# pcb.net
KiCad netlist of a schematic drawn in EasyEDA
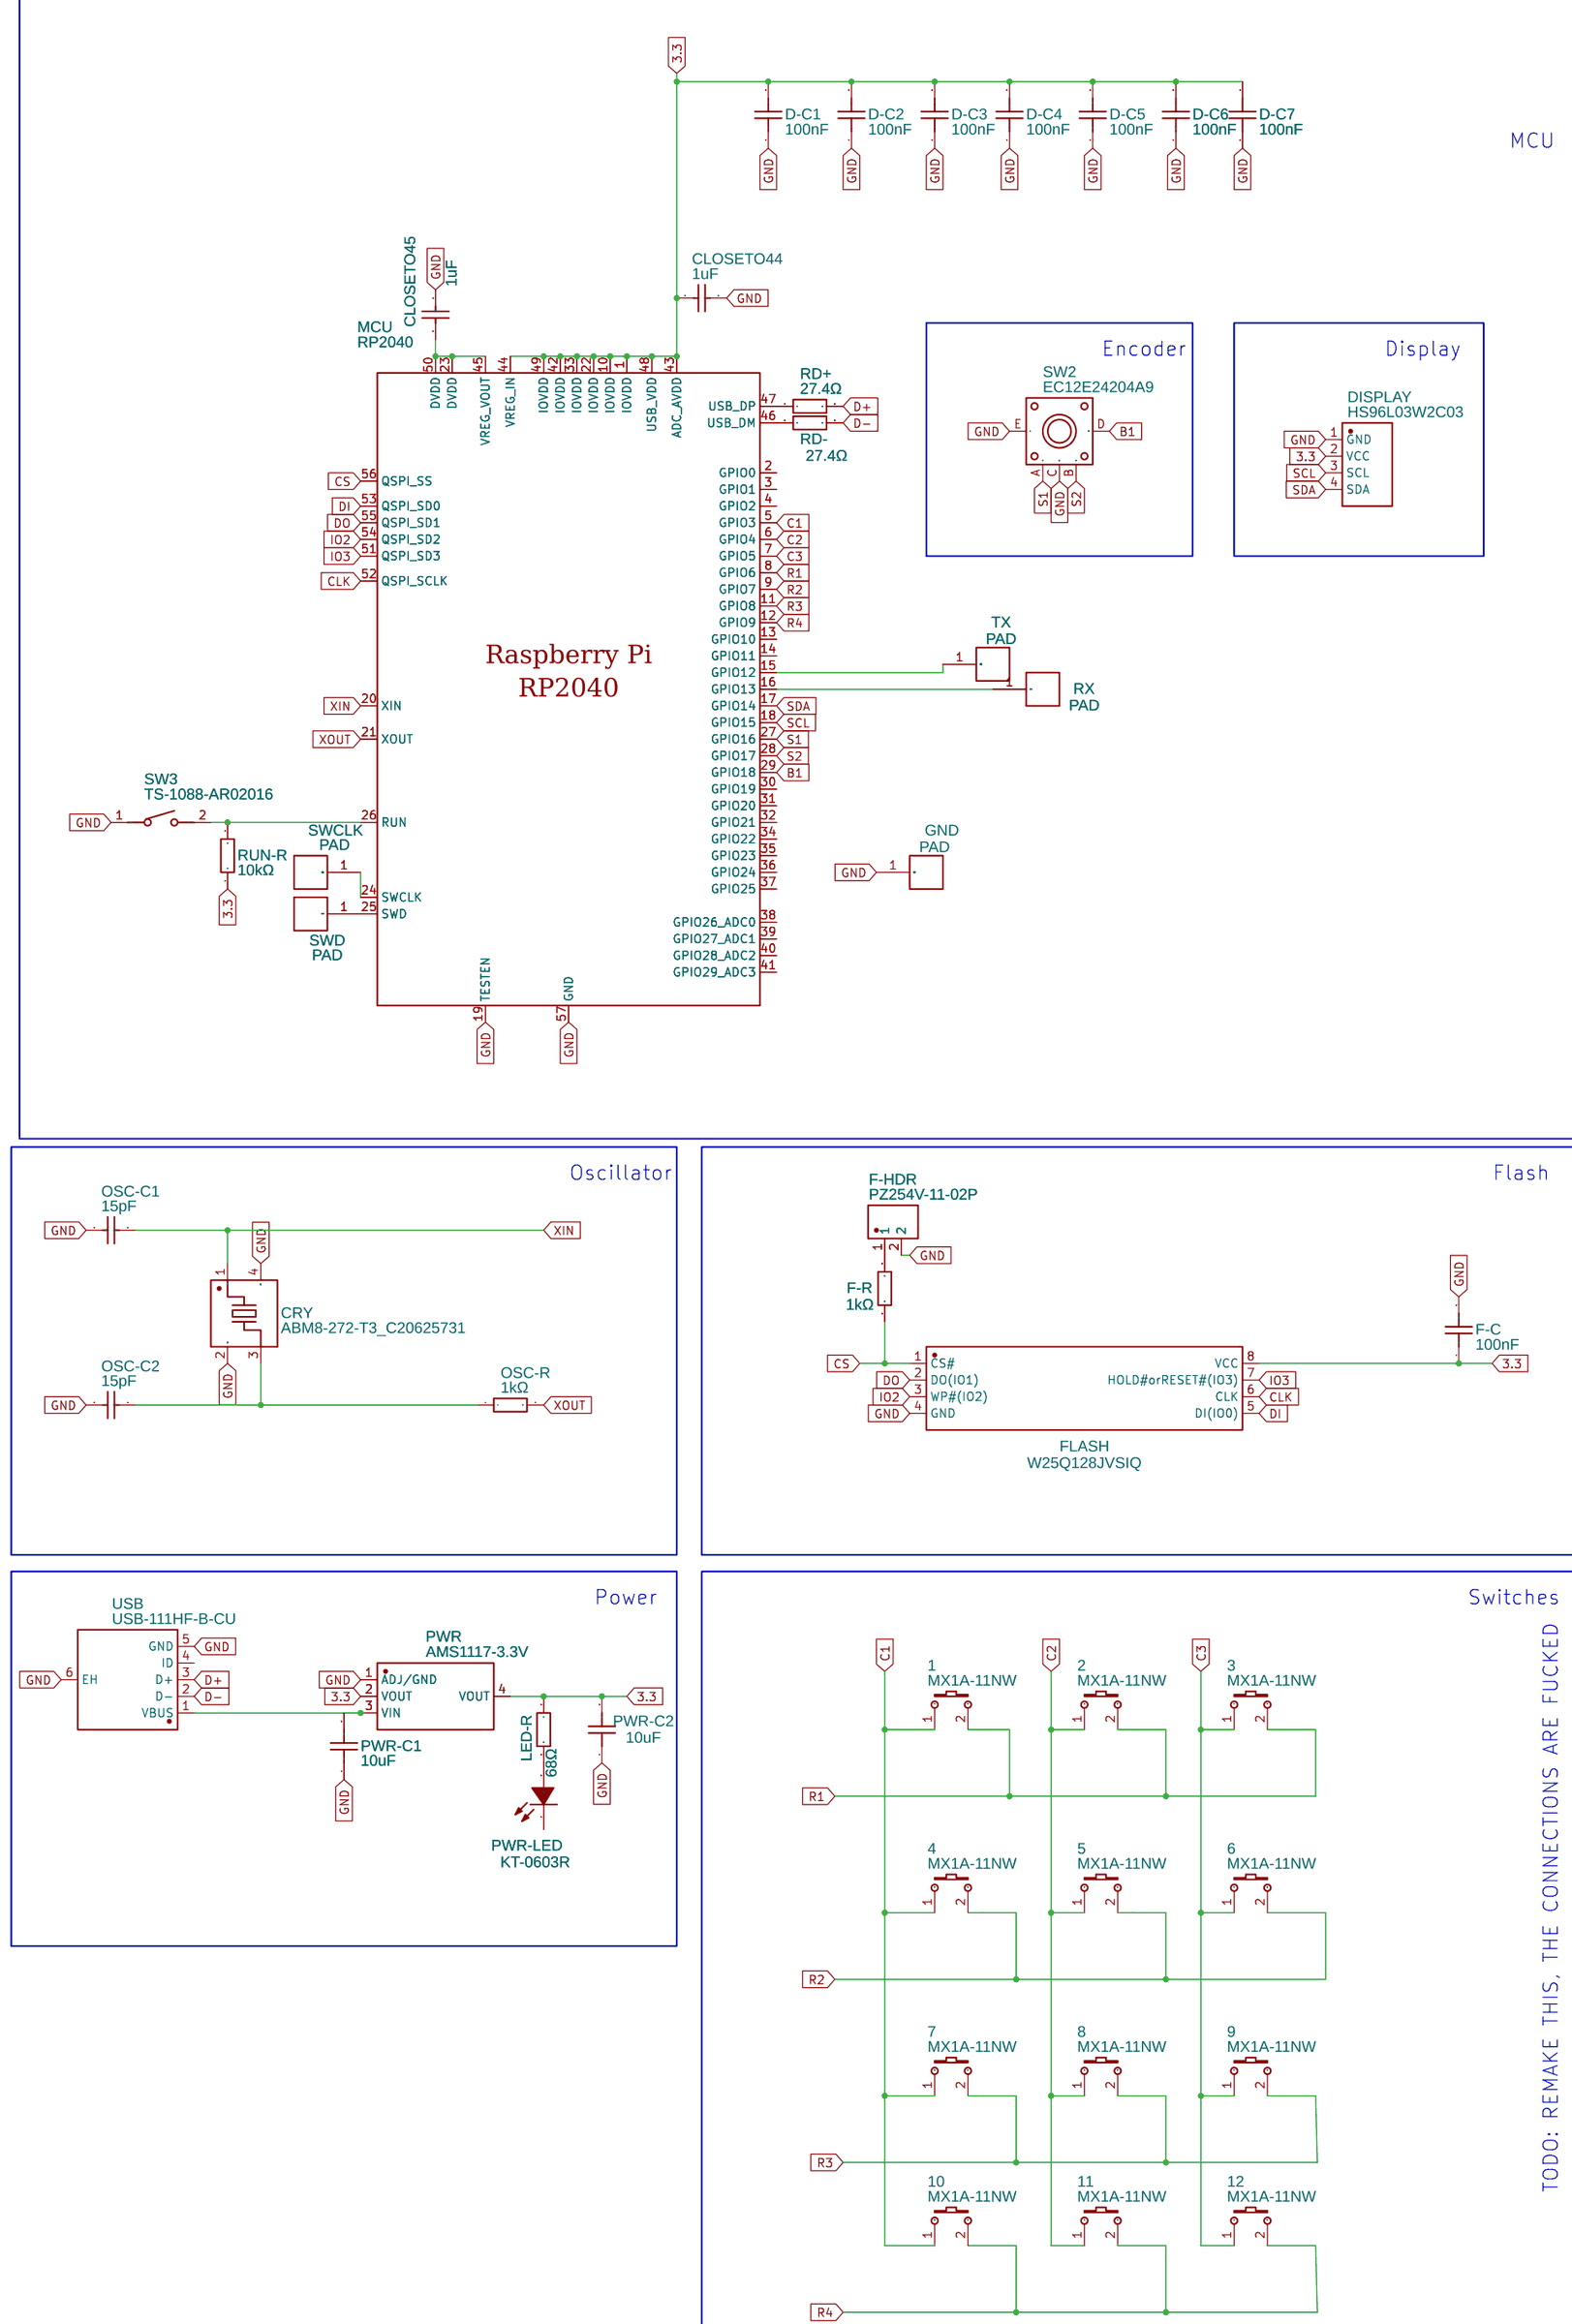
[diagram p0: schematic sheet]

(export (version "E")
  (design (tool "Eeschema 10.0.6"))
  (components
    (comp (ref "1")
      (value "MX1A-11NW")
      (fields (field (name "Manufacturer") "CHERRY"))
      (libsource (lib "") (part "MX1A-11NW"))
    )
    (comp (ref "2")
      (value "MX1A-11NW")
      (fields (field (name "Manufacturer") "CHERRY"))
      (libsource (lib "") (part "MX1A-11NW"))
    )
    (comp (ref "3")
      (value "MX1A-11NW")
      (fields (field (name "Manufacturer") "CHERRY"))
      (libsource (lib "") (part "MX1A-11NW"))
    )
    (comp (ref "4")
      (value "MX1A-11NW")
      (fields (field (name "Manufacturer") "CHERRY"))
      (libsource (lib "") (part "MX1A-11NW"))
    )
    (comp (ref "5")
      (value "MX1A-11NW")
      (fields (field (name "Manufacturer") "CHERRY"))
      (libsource (lib "") (part "MX1A-11NW"))
    )
    (comp (ref "6")
      (value "MX1A-11NW")
      (fields (field (name "Manufacturer") "CHERRY"))
      (libsource (lib "") (part "MX1A-11NW"))
    )
    (comp (ref "7")
      (value "MX1A-11NW")
      (fields (field (name "Manufacturer") "CHERRY"))
      (libsource (lib "") (part "MX1A-11NW"))
    )
    (comp (ref "8")
      (value "MX1A-11NW")
      (fields (field (name "Manufacturer") "CHERRY"))
      (libsource (lib "") (part "MX1A-11NW"))
    )
    (comp (ref "9")
      (value "MX1A-11NW")
      (fields (field (name "Manufacturer") "CHERRY"))
      (libsource (lib "") (part "MX1A-11NW"))
    )
    (comp (ref "10")
      (value "MX1A-11NW")
      (fields (field (name "Manufacturer") "CHERRY"))
      (libsource (lib "") (part "MX1A-11NW"))
    )
    (comp (ref "11")
      (value "MX1A-11NW")
      (fields (field (name "Manufacturer") "CHERRY"))
      (libsource (lib "") (part "MX1A-11NW"))
    )
    (comp (ref "12")
      (value "MX1A-11NW")
      (fields (field (name "Manufacturer") "CHERRY"))
      (libsource (lib "") (part "MX1A-11NW"))
    )
    (comp (ref "CLOSETO44")
      (value "1uF")
      (fields
        (field (name "Manufacturer Part") "GRM155R61E105KA12D")
        (field (name "Manufacturer") "muRata(村田)")
      )
      (libsource (lib "") (part "GRM155R61E105KA12D_1"))
    )
    (comp (ref "CLOSETO45")
      (value "1uF")
      (fields
        (field (name "Manufacturer Part") "GRM155R61E105KA12D")
        (field (name "Manufacturer") "muRata(村田)")
      )
      (libsource (lib "") (part "GRM155R61E105KA12D"))
    )
    (comp (ref "CRY")
      (value "ABM8-272-T3_C20625731")
      (fields (field (name "Manufacturer Part") "ABM8-272-T3") (field (name "Manufacturer") "ABRACON"))
      (libsource (lib "") (part "ABM8-272-T3_C20625731"))
    )
    (comp (ref "D-C1")
      (value "100nF")
      (fields
        (field (name "Manufacturer Part") "CC0603KRX7R9BB104")
        (field (name "Manufacturer") "YAGEO(国巨)")
      )
      (libsource (lib "") (part "CC0603KRX7R9BB104"))
    )
    (comp (ref "D-C2")
      (value "100nF")
      (fields
        (field (name "Manufacturer Part") "CC0603KRX7R9BB104")
        (field (name "Manufacturer") "YAGEO(国巨)")
      )
      (libsource (lib "") (part "CC0603KRX7R9BB104"))
    )
    (comp (ref "D-C3")
      (value "100nF")
      (fields
        (field (name "Manufacturer Part") "CC0603KRX7R9BB104")
        (field (name "Manufacturer") "YAGEO(国巨)")
      )
      (libsource (lib "") (part "CC0603KRX7R9BB104"))
    )
    (comp (ref "D-C4")
      (value "100nF")
      (fields
        (field (name "Manufacturer Part") "CC0603KRX7R9BB104")
        (field (name "Manufacturer") "YAGEO(国巨)")
      )
      (libsource (lib "") (part "CC0603KRX7R9BB104"))
    )
    (comp (ref "D-C5")
      (value "100nF")
      (fields
        (field (name "Manufacturer Part") "CC0603KRX7R9BB104")
        (field (name "Manufacturer") "YAGEO(国巨)")
      )
      (libsource (lib "") (part "CC0603KRX7R9BB104"))
    )
    (comp (ref "D-C6")
      (value "100nF")
      (fields
        (field (name "Manufacturer Part") "CC0603KRX7R9BB104")
        (field (name "Manufacturer") "YAGEO(国巨)")
      )
      (libsource (lib "") (part "CC0603KRX7R9BB104"))
    )
    (comp (ref "D-C7")
      (value "100nF")
      (fields
        (field (name "Manufacturer Part") "CC0603KRX7R9BB104")
        (field (name "Manufacturer") "YAGEO(国巨)")
      )
      (libsource (lib "") (part "CC0603KRX7R9BB104"))
    )
    (comp (ref "DISPLAY")
      (value "HS96L03W2C03")
      (fields (field (name "Manufacturer") "HS(汉昇)"))
      (libsource (lib "") (part "HS96L03W2C03"))
    )
    (comp (ref "F-C")
      (value "100nF")
      (fields
        (field (name "Manufacturer Part") "CC0603KRX7R9BB104")
        (field (name "Manufacturer") "YAGEO(国巨)")
      )
      (libsource (lib "") (part "CC0603KRX7R9BB104_1"))
    )
    (comp (ref "F-HDR")
      (value "PZ254V-11-02P")
      (fields (field (name "Manufacturer") "XFCN(兴飞)"))
      (libsource (lib "") (part "PZ254V-11-02P"))
    )
    (comp (ref "F-R")
      (value "1kΩ")
      (fields
        (field (name "Manufacturer Part") "0805W8F1001T5E")
        (field (name "Manufacturer") "UNI-ROYAL(厚声)")
      )
      (libsource (lib "") (part "0805W8F1001T5E_1"))
    )
    (comp (ref "FLASH")
      (value "W25Q128JVSIQ")
      (fields (field (name "Manufacturer") "WINBOND(华邦)"))
      (libsource (lib "") (part "W25Q128JVSIQ"))
    )
    (comp (ref "GND") (value "PAD") (libsource (lib "") (part "PAD_4")))
    (comp (ref "LED-R")
      (value "68Ω")
      (fields
        (field (name "Manufacturer Part") "1206W4F680JT5E")
        (field (name "Manufacturer") "UNI-ROYAL(厚声)")
      )
      (libsource (lib "") (part "1206W4F680JT5E"))
    )
    (comp (ref "MCU")
      (value "RP2040")
      (fields (field (name "Manufacturer") "Raspberry Pi(树莓派)"))
      (libsource (lib "") (part "RP2040"))
    )
    (comp (ref "OSC-C1")
      (value "15pF")
      (fields (field (name "Manufacturer Part") "0805CG150J500NT") (field (name "Manufacturer") "FH(风华)"))
      (libsource (lib "") (part "0805CG150J500NT"))
    )
    (comp (ref "OSC-C2")
      (value "15pF")
      (fields (field (name "Manufacturer Part") "0805CG150J500NT") (field (name "Manufacturer") "FH(风华)"))
      (libsource (lib "") (part "0805CG150J500NT"))
    )
    (comp (ref "OSC-R")
      (value "1kΩ")
      (fields
        (field (name "Manufacturer Part") "0805W8F1001T5E")
        (field (name "Manufacturer") "UNI-ROYAL(厚声)")
      )
      (libsource (lib "") (part "0805W8F1001T5E"))
    )
    (comp (ref "PWR")
      (value "AMS1117-3.3V")
      (fields (field (name "Manufacturer") "WPMtek(维攀)"))
      (libsource (lib "") (part "AMS1117-3.3V"))
    )
    (comp (ref "PWR-C1")
      (value "10uF")
      (fields
        (field (name "Manufacturer Part") "CL21A106KAYNNNE")
        (field (name "Manufacturer") "SAMSUNG(三星)")
      )
      (libsource (lib "") (part "CL21A106KAYNNNE"))
    )
    (comp (ref "PWR-C2")
      (value "10uF")
      (fields
        (field (name "Manufacturer Part") "CL21A106KAYNNNE")
        (field (name "Manufacturer") "SAMSUNG(三星)")
      )
      (libsource (lib "") (part "CL21A106KAYNNNE"))
    )
    (comp (ref "PWR-LED")
      (value "KT-0603R")
      (fields (field (name "Manufacturer") "KENTO"))
      (libsource (lib "") (part "KT-0603R"))
    )
    (comp (ref "RD+")
      (value "27.4Ω")
      (fields (field (name "Manufacturer Part") "RS-03K27R4FT") (field (name "Manufacturer") "FH(风华)"))
      (libsource (lib "") (part "RS-03K27R4FT"))
    )
    (comp (ref "RD-")
      (value "27.4Ω")
      (fields (field (name "Manufacturer Part") "RS-03K27R4FT") (field (name "Manufacturer") "FH(风华)"))
      (libsource (lib "") (part "RS-03K27R4FT_1"))
    )
    (comp (ref "RUN-R")
      (value "10kΩ")
      (fields
        (field (name "Manufacturer Part") "0805W8F1002T5E")
        (field (name "Manufacturer") "UNI-ROYAL(厚声)")
      )
      (libsource (lib "") (part "0805W8F1002T5E"))
    )
    (comp (ref "RX") (value "PAD") (libsource (lib "") (part "PAD")))
    (comp (ref "SW2")
      (value "EC12E24204A9")
      (fields (field (name "Manufacturer") "ALPSALPINE(阿尔卑斯阿尔派)"))
      (libsource (lib "") (part "EC12E24204A9"))
    )
    (comp (ref "SW3")
      (value "TS-1088-AR02016")
      (fields (field (name "Manufacturer") "XUNPU(讯普)"))
      (libsource (lib "") (part "TS-1088-AR02016"))
    )
    (comp (ref "SWCLK") (value "PAD") (libsource (lib "") (part "PAD_2")))
    (comp (ref "SWD") (value "PAD") (libsource (lib "") (part "PAD_1")))
    (comp (ref "TX") (value "PAD") (libsource (lib "") (part "PAD_3")))
    (comp (ref "USB")
      (value "USB-111HF-B-CU")
      (fields (field (name "Manufacturer") "HOOYA(皓宇电子)"))
      (libsource (lib "") (part "USB-111HF-B-CU"))
    )
  )
  (nets
    (net (code "1") (name "3.3") (class "Default")
      (node (ref "CLOSETO44") (pin "1") (pinfunction "1_1") (pintype "input"))
      (node (ref "D-C1") (pin "2") (pinfunction "2_2") (pintype "unspecified"))
      (node (ref "D-C2") (pin "2") (pinfunction "2_2") (pintype "unspecified"))
      (node (ref "D-C3") (pin "2") (pinfunction "2_2") (pintype "unspecified"))
      (node (ref "D-C4") (pin "2") (pinfunction "2_2") (pintype "unspecified"))
      (node (ref "D-C5") (pin "2") (pinfunction "2_2") (pintype "unspecified"))
      (node (ref "D-C6") (pin "2") (pinfunction "2_2") (pintype "unspecified"))
      (node (ref "D-C7") (pin "2") (pinfunction "2_2") (pintype "unspecified"))
      (node (ref "DISPLAY") (pin "2") (pinfunction "VCC_2") (pintype "unspecified"))
      (node (ref "F-C") (pin "1") (pinfunction "1_1") (pintype "unspecified"))
      (node (ref "FLASH") (pin "8") (pinfunction "VCC_8") (pintype "unspecified"))
      (node (ref "LED-R") (pin "1") (pinfunction "1_1") (pintype "input"))
      (node (ref "MCU") (pin "1") (pinfunction "IOVDD_1") (pintype "bidirectional"))
      (node (ref "MCU") (pin "10") (pinfunction "IOVDD_10") (pintype "bidirectional"))
      (node (ref "MCU") (pin "22") (pinfunction "IOVDD_22") (pintype "bidirectional"))
      (node (ref "MCU") (pin "33") (pinfunction "IOVDD_33") (pintype "bidirectional"))
      (node (ref "MCU") (pin "42") (pinfunction "IOVDD_42") (pintype "bidirectional"))
      (node (ref "MCU") (pin "43") (pinfunction "ADC_AVDD_43") (pintype "bidirectional"))
      (node (ref "MCU") (pin "44") (pinfunction "VREG_IN_44") (pintype "bidirectional"))
      (node (ref "MCU") (pin "48") (pinfunction "USB_VDD_48") (pintype "bidirectional"))
      (node (ref "MCU") (pin "49") (pinfunction "IOVDD_49") (pintype "bidirectional"))
      (node (ref "PWR") (pin "2") (pinfunction "VOUT_2") (pintype "unspecified"))
      (node (ref "PWR") (pin "4") (pinfunction "VOUT_4") (pintype "unspecified"))
      (node (ref "PWR-C2") (pin "2") (pinfunction "2_2") (pintype "unspecified"))
      (node (ref "RUN-R") (pin "2") (pinfunction "2_2") (pintype "input"))
    )
    (net (code "2") (name "B1") (class "Default")
      (node (ref "MCU") (pin "29") (pinfunction "GPIO18_29") (pintype "bidirectional"))
      (node (ref "SW2") (pin "D") (pinfunction "D_D") (pintype "unspecified"))
    )
    (net (code "3") (name "C1") (class "Default")
      (node (ref "1") (pin "1") (pinfunction "1_1") (pintype "unspecified"))
      (node (ref "10") (pin "1") (pinfunction "1_1") (pintype "unspecified"))
      (node (ref "4") (pin "1") (pinfunction "1_1") (pintype "unspecified"))
      (node (ref "7") (pin "1") (pinfunction "1_1") (pintype "unspecified"))
      (node (ref "MCU") (pin "5") (pinfunction "GPIO3_5") (pintype "bidirectional"))
    )
    (net (code "4") (name "C2") (class "Default")
      (node (ref "11") (pin "1") (pinfunction "1_1") (pintype "unspecified"))
      (node (ref "2") (pin "1") (pinfunction "1_1") (pintype "unspecified"))
      (node (ref "5") (pin "1") (pinfunction "1_1") (pintype "unspecified"))
      (node (ref "8") (pin "1") (pinfunction "1_1") (pintype "unspecified"))
      (node (ref "MCU") (pin "6") (pinfunction "GPIO4_6") (pintype "bidirectional"))
    )
    (net (code "5") (name "C3") (class "Default")
      (node (ref "12") (pin "1") (pinfunction "1_1") (pintype "unspecified"))
      (node (ref "3") (pin "1") (pinfunction "1_1") (pintype "unspecified"))
      (node (ref "6") (pin "1") (pinfunction "1_1") (pintype "unspecified"))
      (node (ref "9") (pin "1") (pinfunction "1_1") (pintype "unspecified"))
      (node (ref "MCU") (pin "7") (pinfunction "GPIO5_7") (pintype "bidirectional"))
    )
    (net (code "6") (name "CLK") (class "Default")
      (node (ref "FLASH") (pin "6") (pinfunction "CLK_6") (pintype "unspecified"))
      (node (ref "MCU") (pin "52") (pinfunction "QSPI_SCLK_52") (pintype "output"))
    )
    (net (code "7") (name "CS") (class "Default")
      (node (ref "F-R") (pin "2") (pinfunction "2_2") (pintype "input"))
      (node (ref "FLASH") (pin "1") (pinfunction "CS#_1") (pintype "unspecified"))
      (node (ref "MCU") (pin "56") (pinfunction "QSPI_SS_56") (pintype "bidirectional"))
    )
    (net (code "8") (name "D+") (class "Default")
      (node (ref "RD+") (pin "2") (pinfunction "2_2") (pintype "unspecified"))
      (node (ref "USB") (pin "3") (pinfunction "D+_3") (pintype "unspecified"))
    )
    (net (code "9") (name "D-") (class "Default")
      (node (ref "RD-") (pin "2") (pinfunction "2_2") (pintype "unspecified"))
      (node (ref "USB") (pin "2") (pinfunction "D-_2") (pintype "unspecified"))
    )
    (net (code "10") (name "DI") (class "Default")
      (node (ref "FLASH") (pin "5") (pinfunction "DI(IO0)_5") (pintype "unspecified"))
      (node (ref "MCU") (pin "53") (pinfunction "QSPI_SD0_53") (pintype "bidirectional"))
    )
    (net (code "11") (name "DO") (class "Default")
      (node (ref "FLASH") (pin "2") (pinfunction "DO(IO1)_2") (pintype "unspecified"))
      (node (ref "MCU") (pin "55") (pinfunction "QSPI_SD1_55") (pintype "bidirectional"))
    )
    (net (code "12") (name "GND") (class "Default")
      (node (ref "CLOSETO44") (pin "2") (pinfunction "2_2") (pintype "input"))
      (node (ref "CLOSETO45") (pin "1") (pinfunction "1_1") (pintype "input"))
      (node (ref "CRY") (pin "2") (pinfunction "GND_2") (pintype "input"))
      (node (ref "CRY") (pin "4") (pinfunction "GND_4") (pintype "input"))
      (node (ref "D-C1") (pin "1") (pinfunction "1_1") (pintype "unspecified"))
      (node (ref "D-C2") (pin "1") (pinfunction "1_1") (pintype "unspecified"))
      (node (ref "D-C3") (pin "1") (pinfunction "1_1") (pintype "unspecified"))
      (node (ref "D-C4") (pin "1") (pinfunction "1_1") (pintype "unspecified"))
      (node (ref "D-C5") (pin "1") (pinfunction "1_1") (pintype "unspecified"))
      (node (ref "D-C6") (pin "1") (pinfunction "1_1") (pintype "unspecified"))
      (node (ref "D-C7") (pin "1") (pinfunction "1_1") (pintype "unspecified"))
      (node (ref "DISPLAY") (pin "1") (pinfunction "GND_1") (pintype "unspecified"))
      (node (ref "F-C") (pin "2") (pinfunction "2_2") (pintype "unspecified"))
      (node (ref "F-HDR") (pin "2") (pinfunction "2_2") (pintype "unspecified"))
      (node (ref "FLASH") (pin "4") (pinfunction "GND_4") (pintype "unspecified"))
      (node (ref "GND") (pin "1") (pinfunction "PADPAD123_1") (pintype "unspecified"))
      (node (ref "MCU") (pin "19") (pinfunction "TESTEN_19") (pintype "unspecified"))
      (node (ref "MCU") (pin "57") (pinfunction "GND_57") (pintype "bidirectional"))
      (node (ref "OSC-C1") (pin "2") (pinfunction "2_2") (pintype "input"))
      (node (ref "OSC-C2") (pin "2") (pinfunction "2_2") (pintype "input"))
      (node (ref "PWR") (pin "1") (pinfunction "ADJ/GND_1") (pintype "unspecified"))
      (node (ref "PWR-C1") (pin "1") (pinfunction "1_1") (pintype "unspecified"))
      (node (ref "PWR-C2") (pin "1") (pinfunction "1_1") (pintype "unspecified"))
      (node (ref "SW2") (pin "C") (pinfunction "C_C") (pintype "unspecified"))
      (node (ref "SW2") (pin "E") (pinfunction "E_E") (pintype "unspecified"))
      (node (ref "SW3") (pin "1") (pinfunction "1_1") (pintype "unspecified"))
      (node (ref "USB") (pin "5") (pinfunction "GND_5") (pintype "unspecified"))
      (node (ref "USB") (pin "6") (pinfunction "EH_6") (pintype "unspecified"))
    )
    (net (code "13") (name "IO2") (class "Default")
      (node (ref "FLASH") (pin "3") (pinfunction "WP#(IO2)_3") (pintype "unspecified"))
      (node (ref "MCU") (pin "54") (pinfunction "QSPI_SD2_54") (pintype "bidirectional"))
    )
    (net (code "14") (name "IO3") (class "Default")
      (node (ref "FLASH") (pin "7") (pinfunction "HOLD#orRESET#(IO3)_7") (pintype "unspecified"))
      (node (ref "MCU") (pin "51") (pinfunction "QSPI_SD3_51") (pintype "bidirectional"))
    )
    (net (code "15") (name "Net-(CRY-Pad3)") (class "Default")
      (node (ref "CRY") (pin "3") (pinfunction "3_3") (pintype "input"))
      (node (ref "OSC-C2") (pin "1") (pinfunction "1_1") (pintype "input"))
      (node (ref "OSC-R") (pin "1") (pinfunction "1_1") (pintype "input"))
    )
    (net (code "16") (name "Net-(F-HDR-Pad1)") (class "Default")
      (node (ref "F-HDR") (pin "1") (pinfunction "1_1") (pintype "unspecified"))
      (node (ref "F-R") (pin "1") (pinfunction "1_1") (pintype "input"))
    )
    (net (code "17") (name "Net-(MCU-GPIO12)") (class "Default")
      (node (ref "MCU") (pin "15") (pinfunction "GPIO12_15") (pintype "bidirectional"))
      (node (ref "TX") (pin "1") (pinfunction "PADPAD123_1") (pintype "unspecified"))
    )
    (net (code "18") (name "Net-(MCU-GPIO13)") (class "Default")
      (node (ref "MCU") (pin "16") (pinfunction "GPIO13_16") (pintype "bidirectional"))
      (node (ref "RX") (pin "1") (pinfunction "PADPAD123_1") (pintype "unspecified"))
    )
    (net (code "19") (name "Net-(MCU-RUN)") (class "Default")
      (node (ref "MCU") (pin "26") (pinfunction "RUN_26") (pintype "input"))
      (node (ref "RUN-R") (pin "1") (pinfunction "1_1") (pintype "input"))
      (node (ref "SW3") (pin "2") (pinfunction "2_2") (pintype "unspecified"))
    )
    (net (code "20") (name "Net-(MCU-SWCLK)") (class "Default")
      (node (ref "MCU") (pin "24") (pinfunction "SWCLK_24") (pintype "output"))
      (node (ref "SWCLK") (pin "1") (pinfunction "PADPAD123_1") (pintype "unspecified"))
    )
    (net (code "21") (name "Net-(MCU-SWD)") (class "Default")
      (node (ref "MCU") (pin "25") (pinfunction "SWD_25") (pintype "bidirectional"))
      (node (ref "SWD") (pin "1") (pinfunction "PADPAD123_1") (pintype "unspecified"))
    )
    (net (code "22") (name "Net-(MCU-USB_DM)") (class "Default")
      (node (ref "MCU") (pin "46") (pinfunction "USB_DM_46") (pintype "bidirectional"))
      (node (ref "RD-") (pin "1") (pinfunction "1_1") (pintype "unspecified"))
    )
    (net (code "23") (name "Net-(MCU-USB_DP)") (class "Default")
      (node (ref "MCU") (pin "47") (pinfunction "USB_DP_47") (pintype "bidirectional"))
      (node (ref "RD+") (pin "1") (pinfunction "1_1") (pintype "unspecified"))
    )
    (net (code "24") (name "Net-(MCU-VREG_VOUT)") (class "Default")
      (node (ref "CLOSETO45") (pin "2") (pinfunction "2_2") (pintype "input"))
      (node (ref "MCU") (pin "23") (pinfunction "DVDD_23") (pintype "bidirectional"))
      (node (ref "MCU") (pin "45") (pinfunction "VREG_VOUT_45") (pintype "bidirectional"))
      (node (ref "MCU") (pin "50") (pinfunction "DVDD_50") (pintype "bidirectional"))
    )
    (net (code "25") (name "Net-(PWR-LED-A)") (class "Default")
      (node (ref "LED-R") (pin "2") (pinfunction "2_2") (pintype "input"))
      (node (ref "PWR-LED") (pin "2") (pinfunction "A_2") (pintype "unspecified"))
    )
    (net (code "26") (name "Net-(PWR-VIN)") (class "Default")
      (node (ref "PWR") (pin "3") (pinfunction "VIN_3") (pintype "unspecified"))
      (node (ref "PWR-C1") (pin "2") (pinfunction "2_2") (pintype "unspecified"))
      (node (ref "USB") (pin "1") (pinfunction "VBUS_1") (pintype "unspecified"))
    )
    (net (code "27") (name "R1") (class "Default")
      (node (ref "1") (pin "2") (pinfunction "2_2") (pintype "unspecified"))
      (node (ref "2") (pin "2") (pinfunction "2_2") (pintype "unspecified"))
      (node (ref "3") (pin "2") (pinfunction "2_2") (pintype "unspecified"))
      (node (ref "MCU") (pin "8") (pinfunction "GPIO6_8") (pintype "bidirectional"))
    )
    (net (code "28") (name "R2") (class "Default")
      (node (ref "4") (pin "2") (pinfunction "2_2") (pintype "unspecified"))
      (node (ref "5") (pin "2") (pinfunction "2_2") (pintype "unspecified"))
      (node (ref "6") (pin "2") (pinfunction "2_2") (pintype "unspecified"))
      (node (ref "MCU") (pin "9") (pinfunction "GPIO7_9") (pintype "bidirectional"))
    )
    (net (code "29") (name "R3") (class "Default")
      (node (ref "7") (pin "2") (pinfunction "2_2") (pintype "unspecified"))
      (node (ref "8") (pin "2") (pinfunction "2_2") (pintype "unspecified"))
      (node (ref "9") (pin "2") (pinfunction "2_2") (pintype "unspecified"))
      (node (ref "MCU") (pin "11") (pinfunction "GPIO8_11") (pintype "bidirectional"))
    )
    (net (code "30") (name "R4") (class "Default")
      (node (ref "10") (pin "2") (pinfunction "2_2") (pintype "unspecified"))
      (node (ref "11") (pin "2") (pinfunction "2_2") (pintype "unspecified"))
      (node (ref "12") (pin "2") (pinfunction "2_2") (pintype "unspecified"))
      (node (ref "MCU") (pin "12") (pinfunction "GPIO9_12") (pintype "bidirectional"))
    )
    (net (code "31") (name "S1") (class "Default")
      (node (ref "MCU") (pin "27") (pinfunction "GPIO16_27") (pintype "bidirectional"))
      (node (ref "SW2") (pin "A") (pinfunction "A_A") (pintype "unspecified"))
    )
    (net (code "32") (name "S2") (class "Default")
      (node (ref "MCU") (pin "28") (pinfunction "GPIO17_28") (pintype "bidirectional"))
      (node (ref "SW2") (pin "B") (pinfunction "B_B") (pintype "unspecified"))
    )
    (net (code "33") (name "SCL") (class "Default")
      (node (ref "DISPLAY") (pin "3") (pinfunction "SCL_3") (pintype "unspecified"))
      (node (ref "MCU") (pin "18") (pinfunction "GPIO15_18") (pintype "bidirectional"))
    )
    (net (code "34") (name "SDA") (class "Default")
      (node (ref "DISPLAY") (pin "4") (pinfunction "SDA_4") (pintype "unspecified"))
      (node (ref "MCU") (pin "17") (pinfunction "GPIO14_17") (pintype "bidirectional"))
    )
    (net (code "35") (name "XIN") (class "Default")
      (node (ref "CRY") (pin "1") (pinfunction "1_1") (pintype "input"))
      (node (ref "MCU") (pin "20") (pinfunction "XIN_20") (pintype "input"))
      (node (ref "OSC-C1") (pin "1") (pinfunction "1_1") (pintype "input"))
    )
    (net (code "36") (name "XOUT") (class "Default")
      (node (ref "MCU") (pin "21") (pinfunction "XOUT_21") (pintype "unspecified"))
      (node (ref "OSC-R") (pin "2") (pinfunction "2_2") (pintype "input"))
    )
    (net (code "37") (name "unconnected-(MCU-GPIO0-Pad2)") (class "Default")
      (node (ref "MCU") (pin "2") (pinfunction "GPIO0_2") (pintype "bidirectional"))
    )
    (net (code "38") (name "unconnected-(MCU-GPIO1-Pad3)") (class "Default")
      (node (ref "MCU") (pin "3") (pinfunction "GPIO1_3") (pintype "bidirectional"))
    )
    (net (code "39") (name "unconnected-(MCU-GPIO2-Pad4)") (class "Default")
      (node (ref "MCU") (pin "4") (pinfunction "GPIO2_4") (pintype "bidirectional"))
    )
    (net (code "40") (name "unconnected-(MCU-GPIO10-Pad13)") (class "Default")
      (node (ref "MCU") (pin "13") (pinfunction "GPIO10_13") (pintype "bidirectional"))
    )
    (net (code "41") (name "unconnected-(MCU-GPIO11-Pad14)") (class "Default")
      (node (ref "MCU") (pin "14") (pinfunction "GPIO11_14") (pintype "bidirectional"))
    )
    (net (code "42") (name "unconnected-(MCU-GPIO19-Pad30)") (class "Default")
      (node (ref "MCU") (pin "30") (pinfunction "GPIO19_30") (pintype "bidirectional"))
    )
    (net (code "43") (name "unconnected-(MCU-GPIO20-Pad31)") (class "Default")
      (node (ref "MCU") (pin "31") (pinfunction "GPIO20_31") (pintype "bidirectional"))
    )
    (net (code "44") (name "unconnected-(MCU-GPIO21-Pad32)") (class "Default")
      (node (ref "MCU") (pin "32") (pinfunction "GPIO21_32") (pintype "bidirectional"))
    )
    (net (code "45") (name "unconnected-(MCU-GPIO22-Pad34)") (class "Default")
      (node (ref "MCU") (pin "34") (pinfunction "GPIO22_34") (pintype "bidirectional"))
    )
    (net (code "46") (name "unconnected-(MCU-GPIO23-Pad35)") (class "Default")
      (node (ref "MCU") (pin "35") (pinfunction "GPIO23_35") (pintype "bidirectional"))
    )
    (net (code "47") (name "unconnected-(MCU-GPIO24-Pad36)") (class "Default")
      (node (ref "MCU") (pin "36") (pinfunction "GPIO24_36") (pintype "bidirectional"))
    )
    (net (code "48") (name "unconnected-(MCU-GPIO25-Pad37)") (class "Default")
      (node (ref "MCU") (pin "37") (pinfunction "GPIO25_37") (pintype "bidirectional"))
    )
    (net (code "49") (name "unconnected-(MCU-GPIO26_ADC0-Pad38)") (class "Default")
      (node (ref "MCU") (pin "38") (pinfunction "GPIO26_ADC0_38") (pintype "bidirectional"))
    )
    (net (code "50") (name "unconnected-(MCU-GPIO27_ADC1-Pad39)") (class "Default")
      (node (ref "MCU") (pin "39") (pinfunction "GPIO27_ADC1_39") (pintype "bidirectional"))
    )
    (net (code "51") (name "unconnected-(MCU-GPIO28_ADC2-Pad40)") (class "Default")
      (node (ref "MCU") (pin "40") (pinfunction "GPIO28_ADC2_40") (pintype "bidirectional"))
    )
    (net (code "52") (name "unconnected-(MCU-GPIO29_ADC3-Pad41)") (class "Default")
      (node (ref "MCU") (pin "41") (pinfunction "GPIO29_ADC3_41") (pintype "bidirectional"))
    )
    (net (code "53") (name "unconnected-(PWR-LED-K-Pad1)") (class "Default")
      (node (ref "PWR-LED") (pin "1") (pinfunction "K_1") (pintype "unspecified"))
    )
    (net (code "54") (name "unconnected-(USB-ID-Pad4)") (class "Default")
      (node (ref "USB") (pin "4") (pinfunction "ID_4") (pintype "unspecified"))
    )
  )
)
